# 02_Connectors.net
KiCad netlist of a schematic drawn in Altium Designer
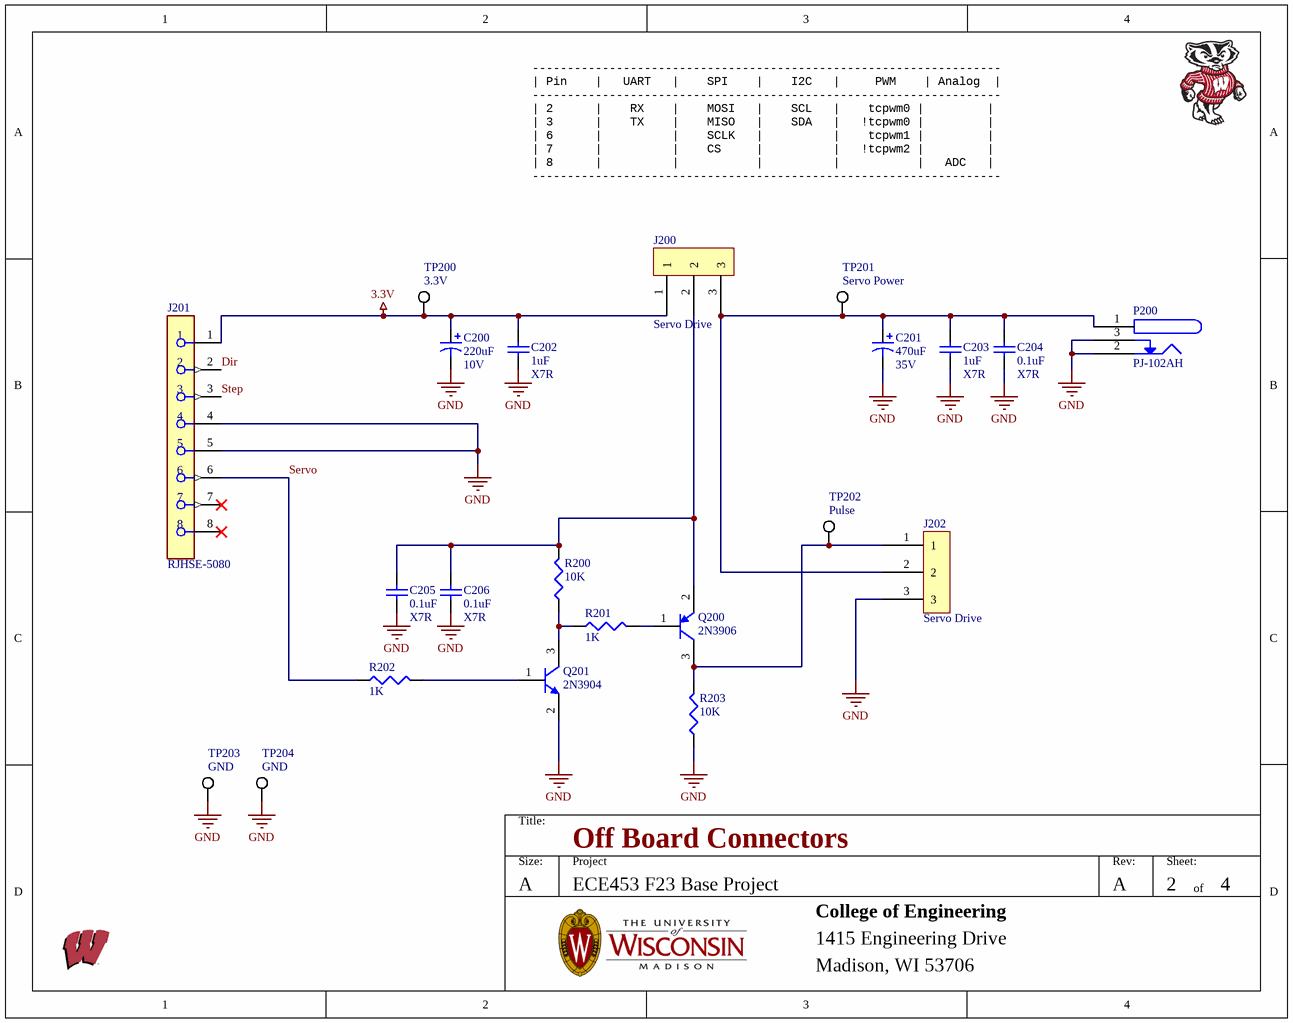
[diagram p0: 02_Connectors.SchDoc]

(export (version "E")
  (design (tool "Eeschema 10.0.6"))
  (components
    (comp (ref "C200")
      (value "220uF")
      (footprint "CAPPR2-5x11")
      (description "Capacitor Al 105deg 220uF 10V 5X11")
      (fields
        (field (name "MANUFACTURER") "Rubycon")
        (field (name "MANUFACTURER PART NUMBER") "10YXJ220M5X11")
        (field (name "VOLTAGE") "10V")
      )
      (libsource (lib "ECE453") (part "Cap Pol1_1"))
    )
    (comp (ref "C201")
      (value "470uF")
      (footprint "CAPPR5-10x12.5")
      (description "CAP ALUM 470UF 20% 35V RADIAL")
      (fields
        (field (name "VOLTAGE") "35V")
        (field (name "MANUFACTURER") "Rubycon")
        (field (name "TOLERANCE") "20%")
      )
      (libsource (lib "ECE453") (part "Cap Pol3_1"))
    )
    (comp (ref "C202")
      (value "1uF")
      (footprint "CAPC2012M")
      (description "CAP CER 1UF 50V X7R 0805")
      (fields
        (field (name "MANUFACTURER") "Samsung")
        (field (name "MANUFACTURER PART NUMBER") "CL21B105KBFNNNE")
        (field (name "DIELECTRIC") "X7R")
      )
      (libsource (lib "ECE453") (part "Cap_5"))
    )
    (comp (ref "C203")
      (value "1uF")
      (footprint "CAPC2012M")
      (description "CAP CER 1UF 50V X7R 0805")
      (fields
        (field (name "MANUFACTURER") "Samsung")
        (field (name "MANUFACTURER PART NUMBER") "CL21B105KBFNNNE")
        (field (name "DIELECTRIC") "X7R")
      )
      (libsource (lib "ECE453") (part "Cap"))
    )
    (comp (ref "C204")
      (value "0.1uF")
      (footprint "CAPC2012M")
      (description "Cap Ceramic 0.1uF 50V X7R 20% SMD 0805 125°C Plastic T/R")
      (fields
        (field (name "MANUFACTURER") "KEMET")
        (field (name "MANUFACTURER PART NUMBER") "C0805C104M5RAC7210")
        (field (name "DIELECTRIC") "X7R")
      )
      (libsource (lib "ECE453") (part "Cap_1"))
    )
    (comp (ref "C205")
      (value "0.1uF")
      (footprint "CAPC2012M")
      (description "Cap Ceramic 0.1uF 50V X7R 20% SMD 0805 125°C Plastic T/R")
      (fields
        (field (name "MANUFACTURER") "KEMET")
        (field (name "MANUFACTURER PART NUMBER") "C0805C104M5RAC7210")
        (field (name "DIELECTRIC") "X7R")
      )
      (libsource (lib "ECE453") (part "Cap_1"))
    )
    (comp (ref "C206")
      (value "0.1uF")
      (footprint "CAPC2012M")
      (description "Cap Ceramic 0.1uF 50V X7R 20% SMD 0805 125°C Plastic T/R")
      (fields
        (field (name "MANUFACTURER") "KEMET")
        (field (name "MANUFACTURER PART NUMBER") "C0805C104M5RAC7210")
        (field (name "DIELECTRIC") "X7R")
      )
      (libsource (lib "ECE453") (part "Cap_1"))
    )
    (comp (ref "J200")
      (value "Servo Drive")
      (footprint "3X1HDR")
      (description "Switch Slide N.O./N.C. SPDT Top Slide 0.2A 30VDC PC Pins Thru-Hole")
      (fields (field (name "MANUFACTURER") "E-Switch") (field (name "MANUFACTURER PART NUMBER") "EG1218"))
      (libsource (lib "ECE453") (part "3-Pin_1"))
    )
    (comp (ref "J201")
      (value "RJHSE-5080")
      (footprint "FP-RJHSE-5080-MFG")
      (description "CONN MOD JACK 8P8C R/A UNSHLD")
      (fields
        (field (name "OCTOPART") "https://octopart.com/rjhse-5080-amphenol-45060")
        (field (name "MANUFACTURER") "Amphenol")
      )
      (libsource (lib "Altium Content Vault") (part "b0a0b555dd3abf3683e7c330df25cc4"))
    )
    (comp (ref "J202")
      (value "Servo Drive")
      (footprint "3X1HDR")
      (description "Switch Slide N.O./N.C. SPDT Top Slide 0.2A 30VDC PC Pins Thru-Hole")
      (fields (field (name "MANUFACTURER") "E-Switch") (field (name "MANUFACTURER PART NUMBER") "EG1218"))
      (libsource (lib "") (part "3-Pin_1_1"))
    )
    (comp (ref "P200")
      (value "PJ-102")
      (footprint "PJ-102")
      (description "CONN PWR JACK 2.1X5.5MM HIGH CUR")
      (fields (field (name "MANUFACTURER") "CUI Inc") (field (name "MANUFACTURER PART NUMBER") "PJ-102AH"))
      (libsource (lib "ECE453") (part "CONN JACK PWR W/SW"))
    )
    (comp (ref "Q200")
      (value "2N3906")
      (footprint "SOT23-3M")
      (description "TRANS PNP 40V 0.2A SOT23")
      (fields
        (field (name "MANUFACTURER PART NUMBER") "MMBT3906LT1G")
        (field (name "MANUFACTURER") "ON Semiconductor")
      )
      (libsource (lib "ECE453") (part "2N3906"))
    )
    (comp (ref "Q201")
      (value "2N3904")
      (footprint "SOT23-3M")
      (description "NPN General Purpose Amplifier")
      (fields
        (field (name "MANUFACTURER PART NUMBER") "MMBT3904-7-F")
        (field (name "MANUFACTURER") "Diodes Incorporated")
      )
      (libsource (lib "ECE453") (part "2N3904"))
    )
    (comp (ref "R200")
      (value "10K")
      (footprint "RES_0805")
      (description "Res Thick Film 0805 10K Ohm 1% 0.125W ±100ppm/°C Molded SMD Paper T/R")
      (fields
        (field (name "MANUFACTURER") "Stackpole Electronics")
        (field (name "MANUFACTURER PART NUMBER") "RMCF0805FT10K0")
      )
      (libsource (lib "ECE453") (part "Res3"))
    )
    (comp (ref "R201")
      (value "1K")
      (footprint "ECE453:RES_0805")
      (description "Res Thick Film 0805 1K Ohm 1% 0.125W(1/8W) ±100ppm/C Pad SMD Automotive T/R")
      (fields
        (field (name "MANUFACTURER") "Stackpole Electronics")
        (field (name "MANUFACTURER PART NUMBER") "RMCF0805FT1K00")
      )
      (libsource (lib "ECE453") (part "Res3_1"))
    )
    (comp (ref "R202")
      (value "1K")
      (footprint "ECE453:RES_0805")
      (description "Res Thick Film 0805 1K Ohm 1% 0.125W(1/8W) ±100ppm/C Pad SMD Automotive T/R")
      (fields
        (field (name "MANUFACTURER") "Stackpole Electronics")
        (field (name "MANUFACTURER PART NUMBER") "RMCF0805FT1K00")
      )
      (libsource (lib "ECE453") (part "Res3_1"))
    )
    (comp (ref "R203")
      (value "10K")
      (footprint "RES_0805")
      (description "Res Thick Film 0805 10K Ohm 1% 0.125W ±100ppm/°C Molded SMD Paper T/R")
      (fields
        (field (name "MANUFACTURER") "Stackpole Electronics")
        (field (name "MANUFACTURER PART NUMBER") "RMCF0805FT10K0")
      )
      (libsource (lib "ECE453") (part "Res3"))
    )
    (comp (ref "TP200")
      (value "3.3V")
      (footprint "KSTN-5019_V")
      (description "Test Point, 1 Position SMD, RoHS, Tape and Reel")
      (fields
        (field (name "MANUFACTURER") "Keystone Electronics")
        (field (name "MANUFACTURER PART NUMBER") "5019")
      )
      (libsource (lib "ECE453") (part "CMP-1672-00008-1"))
    )
    (comp (ref "TP201")
      (value "Servo Power")
      (footprint "KSTN-5019_V")
      (description "Test Point, 1 Position SMD, RoHS, Tape and Reel")
      (fields
        (field (name "MANUFACTURER") "Keystone Electronics")
        (field (name "MANUFACTURER PART NUMBER") "5019")
      )
      (libsource (lib "ECE453") (part "CMP-1672-00008-1"))
    )
    (comp (ref "TP202")
      (value "Pulse")
      (footprint "KSTN-5019_V")
      (description "Test Point, 1 Position SMD, RoHS, Tape and Reel")
      (fields
        (field (name "MANUFACTURER") "Keystone Electronics")
        (field (name "MANUFACTURER PART NUMBER") "5019")
      )
      (libsource (lib "ECE453") (part "CMP-1672-00008-1"))
    )
    (comp (ref "TP203")
      (value "GND")
      (footprint "KSTN-5019_V")
      (description "Test Point, 1 Position SMD, RoHS, Tape and Reel")
      (fields
        (field (name "MANUFACTURER") "Keystone Electronics")
        (field (name "MANUFACTURER PART NUMBER") "5019")
      )
      (libsource (lib "ECE453") (part "CMP-1672-00008-1"))
    )
    (comp (ref "TP204")
      (value "GND")
      (footprint "KSTN-5019_V")
      (description "Test Point, 1 Position SMD, RoHS, Tape and Reel")
      (fields
        (field (name "MANUFACTURER") "Keystone Electronics")
        (field (name "MANUFACTURER PART NUMBER") "5019")
      )
      (libsource (lib "ECE453") (part "CMP-1672-00008-1"))
    )
  )
  (nets
    (net (code "1") (name "/Dir") (class "Default")
      (node (ref "J201") (pin "2") (pinfunction "2_2") (pintype "output"))
    )
    (net (code "2") (name "/Servo") (class "Default")
      (node (ref "J201") (pin "6") (pinfunction "6_6") (pintype "output"))
      (node (ref "R202") (pin "1") (pinfunction "1_1") (pintype "passive"))
    )
    (net (code "3") (name "/Step") (class "Default")
      (node (ref "J201") (pin "3") (pinfunction "3_3") (pintype "output"))
    )
    (net (code "4") (name "3.3V") (class "Default")
      (node (ref "C200") (pin "1") (pinfunction "1_1") (pintype "passive"))
      (node (ref "C202") (pin "1") (pinfunction "1_1") (pintype "passive"))
      (node (ref "J200") (pin "1") (pinfunction "1_1") (pintype "passive"))
      (node (ref "J201") (pin "1") (pinfunction "1_1") (pintype "passive"))
      (node (ref "TP200") (pin "1") (pinfunction "1_1") (pintype "passive"))
    )
    (net (code "5") (name "GND") (class "Default")
      (node (ref "C200") (pin "2") (pinfunction "2_2") (pintype "passive"))
      (node (ref "C201") (pin "2") (pinfunction "2_2") (pintype "passive"))
      (node (ref "C202") (pin "2") (pinfunction "2_2") (pintype "passive"))
      (node (ref "C203") (pin "1") (pinfunction "1_1") (pintype "passive"))
      (node (ref "C204") (pin "2") (pinfunction "2_2") (pintype "passive"))
      (node (ref "C205") (pin "2") (pinfunction "2_2") (pintype "passive"))
      (node (ref "C206") (pin "2") (pinfunction "2_2") (pintype "passive"))
      (node (ref "J201") (pin "4") (pinfunction "4_4") (pintype "passive"))
      (node (ref "J201") (pin "5") (pinfunction "5_5") (pintype "passive"))
      (node (ref "J202") (pin "3") (pinfunction "3_3") (pintype "passive"))
      (node (ref "P200") (pin "2") (pinfunction "2_2") (pintype "passive"))
      (node (ref "P200") (pin "3") (pinfunction "3_3") (pintype "passive"))
      (node (ref "Q201") (pin "2") (pinfunction "E_2") (pintype "passive"))
      (node (ref "R203") (pin "1") (pinfunction "1_1") (pintype "passive"))
      (node (ref "TP203") (pin "1") (pinfunction "1_1") (pintype "passive"))
      (node (ref "TP204") (pin "1") (pinfunction "1_1") (pintype "passive"))
    )
    (net (code "6") (name "Net-(C201-Pad1)") (class "Default")
      (node (ref "C201") (pin "1") (pinfunction "1_1") (pintype "passive"))
      (node (ref "C203") (pin "2") (pinfunction "2_2") (pintype "passive"))
      (node (ref "C204") (pin "1") (pinfunction "1_1") (pintype "passive"))
      (node (ref "J200") (pin "3") (pinfunction "3_3") (pintype "passive"))
      (node (ref "J202") (pin "2") (pinfunction "2_2") (pintype "passive"))
      (node (ref "P200") (pin "1") (pinfunction "1_1") (pintype "passive"))
      (node (ref "TP201") (pin "1") (pinfunction "1_1") (pintype "passive"))
    )
    (net (code "7") (name "Net-(Q200-B)") (class "Default")
      (node (ref "Q200") (pin "1") (pinfunction "B_1") (pintype "passive"))
      (node (ref "R201") (pin "2") (pinfunction "2_2") (pintype "passive"))
    )
    (net (code "8") (name "Net-(Q200-C)") (class "Default")
      (node (ref "J202") (pin "1") (pinfunction "1_1") (pintype "passive"))
      (node (ref "Q200") (pin "3") (pinfunction "C_3") (pintype "passive"))
      (node (ref "R203") (pin "2") (pinfunction "2_2") (pintype "passive"))
      (node (ref "TP202") (pin "1") (pinfunction "1_1") (pintype "passive"))
    )
    (net (code "9") (name "Net-(Q200-E)") (class "Default")
      (node (ref "C205") (pin "1") (pinfunction "1_1") (pintype "passive"))
      (node (ref "C206") (pin "1") (pinfunction "1_1") (pintype "passive"))
      (node (ref "J200") (pin "2") (pinfunction "2_2") (pintype "passive"))
      (node (ref "Q200") (pin "2") (pinfunction "E_2") (pintype "passive"))
      (node (ref "R200") (pin "2") (pinfunction "2_2") (pintype "passive"))
    )
    (net (code "10") (name "Net-(Q201-B)") (class "Default")
      (node (ref "Q201") (pin "1") (pinfunction "B_1") (pintype "passive"))
      (node (ref "R202") (pin "2") (pinfunction "2_2") (pintype "passive"))
    )
    (net (code "11") (name "Net-(Q201-C)") (class "Default")
      (node (ref "Q201") (pin "3") (pinfunction "C_3") (pintype "passive"))
      (node (ref "R200") (pin "1") (pinfunction "1_1") (pintype "passive"))
      (node (ref "R201") (pin "1") (pinfunction "1_1") (pintype "passive"))
    )
    (net (code "12") (name "unconnected-(J201-Pad7)") (class "Default")
      (node (ref "J201") (pin "7") (pinfunction "7_7") (pintype "output+no_connect"))
    )
    (net (code "13") (name "unconnected-(J201-Pad8)") (class "Default")
      (node (ref "J201") (pin "8") (pinfunction "8_8") (pintype "passive+no_connect"))
    )
  )
)
